# Leak_Detector_Remote.net
KiCad netlist of a schematic drawn in EAGLE
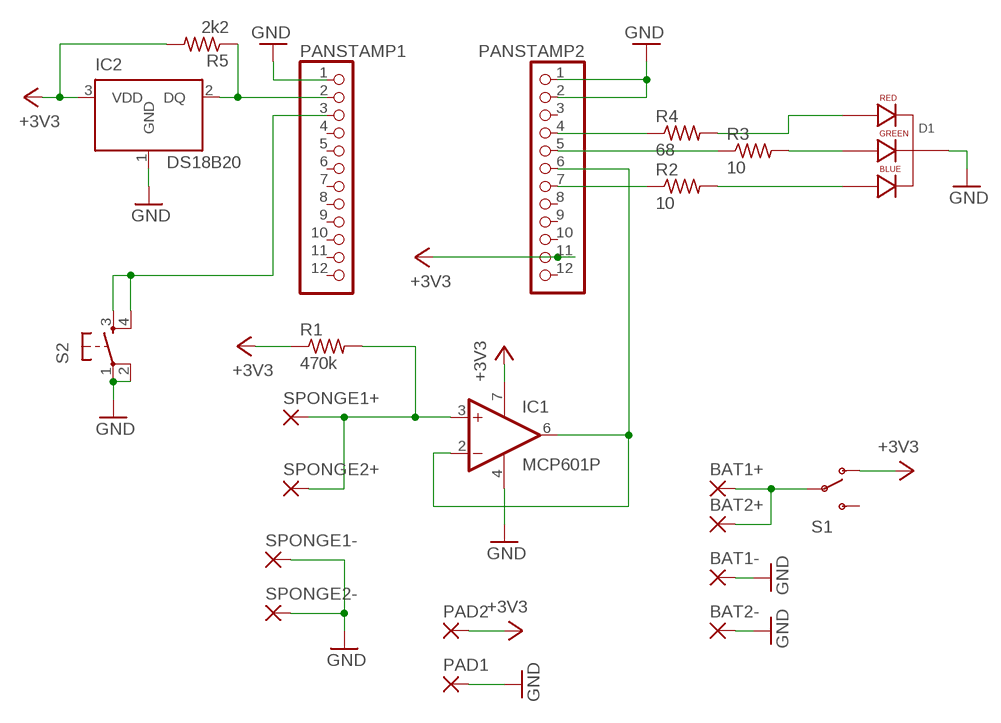
[diagram p0: schematic, sheet 1]

(export (version "E")
  (design (tool "Eeschema 10.0.6"))
  (components
    (comp (ref "BAT1+")
      (value "3,81/1,4")
      (footprint "eagle-import:3,81_1,4")
      (libsource (lib "eagle-import") (part "3,81/1,4"))
    )
    (comp (ref "BAT1-")
      (value "3,81/1,4")
      (footprint "eagle-import:3,81_1,4")
      (libsource (lib "eagle-import") (part "3,81/1,4"))
    )
    (comp (ref "BAT2+")
      (value "3,81/1,4")
      (footprint "eagle-import:3,81_1,4")
      (libsource (lib "eagle-import") (part "3,81/1,4"))
    )
    (comp (ref "BAT2-")
      (value "3,81/1,4")
      (footprint "eagle-import:3,81_1,4")
      (libsource (lib "eagle-import") (part "3,81/1,4"))
    )
    (comp (ref "D1")
      (value "LED-RGB-CC-THRUCLEAR")
      (footprint "eagle-import:LED-RGB-THRU")
      (libsource (lib "eagle-import") (part "LED-RGB-CC-THRUCLEAR"))
    )
    (comp (ref "IC1")
      (value "MCP601P")
      (footprint "eagle-import:DIL08")
      (libsource (lib "eagle-import") (part "MCP601P"))
    )
    (comp (ref "IC2")
      (value "DS18B20")
      (footprint "eagle-import:TO-92")
      (libsource (lib "eagle-import") (part "DS1820"))
    )
    (comp (ref "PAD1")
      (value "1,6/0,9")
      (footprint "eagle-import:1,6_0,9")
      (libsource (lib "eagle-import") (part "1,6/0,9"))
    )
    (comp (ref "PAD2")
      (value "1,6/0,9")
      (footprint "eagle-import:1,6_0,9")
      (libsource (lib "eagle-import") (part "1,6/0,9"))
    )
    (comp (ref "PANSTAMP1")
      (value "PINHD-1X12")
      (footprint "eagle-import:1X12")
      (libsource (lib "eagle-import") (part "PINHD-1X12"))
    )
    (comp (ref "PANSTAMP2")
      (value "PINHD-1X12")
      (footprint "eagle-import:1X12")
      (libsource (lib "eagle-import") (part "PINHD-1X12"))
    )
    (comp (ref "R1")
      (value "470k")
      (footprint "eagle-import:0204_7")
      (libsource (lib "eagle-import") (part "R-US_0204/7"))
    )
    (comp (ref "R2")
      (value "10")
      (footprint "eagle-import:0204_7")
      (libsource (lib "eagle-import") (part "R-US_0204/7"))
    )
    (comp (ref "R3")
      (value "10")
      (footprint "eagle-import:0204_7")
      (libsource (lib "eagle-import") (part "R-US_0204/7"))
    )
    (comp (ref "R4")
      (value "68")
      (footprint "eagle-import:0204_7")
      (libsource (lib "eagle-import") (part "R-US_0204/7"))
    )
    (comp (ref "R5")
      (value "2k2")
      (footprint "eagle-import:0204_7")
      (libsource (lib "eagle-import") (part "R-US_0204/7"))
    )
    (comp (ref "S1")
      (value "SWITCH-SPDTKIT")
      (footprint "eagle-import:SWITCH-SPDT_KIT")
      (libsource (lib "eagle-import") (part "SWITCH-SPDTKIT"))
    )
    (comp (ref "S2")
      (value "TAC_SWITCHPTH")
      (footprint "eagle-import:TACTILE-PTH")
      (libsource (lib "eagle-import") (part "TAC_SWITCHPTH"))
    )
    (comp (ref "SPONGE1+")
      (value "3,81/1,4")
      (footprint "eagle-import:3,81_1,4")
      (libsource (lib "eagle-import") (part "3,81/1,4"))
    )
    (comp (ref "SPONGE1-")
      (value "3,81/1,4")
      (footprint "eagle-import:3,81_1,4")
      (libsource (lib "eagle-import") (part "3,81/1,4"))
    )
    (comp (ref "SPONGE2+")
      (value "3,81/1,4")
      (footprint "eagle-import:3,81_1,4")
      (libsource (lib "eagle-import") (part "3,81/1,4"))
    )
    (comp (ref "SPONGE2-")
      (value "3,81/1,4")
      (footprint "eagle-import:3,81_1,4")
      (libsource (lib "eagle-import") (part "3,81/1,4"))
    )
  )
  (nets
    (net (code "1") (name "+3V3") (class "Default")
      (node (ref "IC1") (pin "7") (pinfunction "V+_7") (pintype "power_in"))
      (node (ref "IC2") (pin "3") (pinfunction "VDD_3") (pintype "input"))
      (node (ref "PAD2") (pin "1") (pinfunction "P_1") (pintype "passive"))
      (node (ref "PANSTAMP2") (pin "11") (pinfunction "11_11") (pintype "passive"))
      (node (ref "R1") (pin "1") (pinfunction "1_1") (pintype "passive"))
      (node (ref "R5") (pin "2") (pinfunction "2_2") (pintype "passive"))
      (node (ref "S1") (pin "1") (pinfunction "O_1") (pintype "passive"))
    )
    (net (code "2") (name "GND") (class "Default")
      (node (ref "BAT1-") (pin "1") (pinfunction "P_1") (pintype "passive"))
      (node (ref "BAT2-") (pin "1") (pinfunction "P_1") (pintype "passive"))
      (node (ref "D1") (pin "2") (pinfunction "CATHODE_2") (pintype "bidirectional"))
      (node (ref "IC1") (pin "4") (pinfunction "V-_4") (pintype "power_in"))
      (node (ref "IC2") (pin "1") (pinfunction "GND_1") (pintype "power_in"))
      (node (ref "PAD1") (pin "1") (pinfunction "P_1") (pintype "passive"))
      (node (ref "PANSTAMP1") (pin "1") (pinfunction "1_1") (pintype "passive"))
      (node (ref "PANSTAMP2") (pin "1") (pinfunction "1_1") (pintype "passive"))
      (node (ref "PANSTAMP2") (pin "2") (pinfunction "2_2") (pintype "passive"))
      (node (ref "S2") (pin "1") (pinfunction "1_1") (pintype "passive"))
      (node (ref "S2") (pin "2") (pinfunction "2_2") (pintype "passive"))
      (node (ref "SPONGE1-") (pin "1") (pinfunction "P_1") (pintype "passive"))
      (node (ref "SPONGE2-") (pin "1") (pinfunction "P_1") (pintype "passive"))
    )
    (net (code "3") (name "Net-(BAT1+-P)") (class "Default")
      (node (ref "BAT1+") (pin "1") (pinfunction "P_1") (pintype "passive"))
      (node (ref "BAT2+") (pin "1") (pinfunction "P_1") (pintype "passive"))
      (node (ref "S1") (pin "2") (pinfunction "P_2") (pintype "passive"))
    )
    (net (code "4") (name "Net-(D1-BLUE_CATHODE)") (class "Default")
      (node (ref "D1") (pin "4") (pinfunction "BLUE_CATHODE_4") (pintype "bidirectional"))
      (node (ref "R2") (pin "2") (pinfunction "2_2") (pintype "passive"))
    )
    (net (code "5") (name "Net-(D1-GREEN_CATHODE)") (class "Default")
      (node (ref "D1") (pin "3") (pinfunction "GREEN_CATHODE_3") (pintype "bidirectional"))
      (node (ref "R3") (pin "2") (pinfunction "2_2") (pintype "passive"))
    )
    (net (code "6") (name "Net-(D1-RED_CATHODE)") (class "Default")
      (node (ref "D1") (pin "1") (pinfunction "RED_CATHODE_1") (pintype "bidirectional"))
      (node (ref "R4") (pin "2") (pinfunction "2_2") (pintype "passive"))
    )
    (net (code "7") (name "Net-(IC1-+IN)") (class "Default")
      (node (ref "IC1") (pin "3") (pinfunction "+IN_3") (pintype "input"))
      (node (ref "R1") (pin "2") (pinfunction "2_2") (pintype "passive"))
      (node (ref "SPONGE1+") (pin "1") (pinfunction "P_1") (pintype "passive"))
      (node (ref "SPONGE2+") (pin "1") (pinfunction "P_1") (pintype "passive"))
    )
    (net (code "8") (name "Net-(IC1--IN)") (class "Default")
      (node (ref "IC1") (pin "2") (pinfunction "-IN_2") (pintype "input"))
      (node (ref "IC1") (pin "6") (pinfunction "OUT_6") (pintype "output"))
      (node (ref "PANSTAMP2") (pin "6") (pinfunction "6_6") (pintype "passive"))
    )
    (net (code "9") (name "Net-(IC2-DQ)") (class "Default")
      (node (ref "IC2") (pin "2") (pinfunction "DQ_2") (pintype "output"))
      (node (ref "PANSTAMP1") (pin "2") (pinfunction "2_2") (pintype "passive"))
      (node (ref "R5") (pin "1") (pinfunction "1_1") (pintype "passive"))
    )
    (net (code "10") (name "Net-(PANSTAMP1-Pad3)") (class "Default")
      (node (ref "PANSTAMP1") (pin "3") (pinfunction "3_3") (pintype "passive"))
      (node (ref "S2") (pin "3") (pinfunction "3_3") (pintype "passive"))
      (node (ref "S2") (pin "4") (pinfunction "4_4") (pintype "passive"))
    )
    (net (code "11") (name "Net-(PANSTAMP2-Pad4)") (class "Default")
      (node (ref "PANSTAMP2") (pin "4") (pinfunction "4_4") (pintype "passive"))
      (node (ref "R4") (pin "1") (pinfunction "1_1") (pintype "passive"))
    )
    (net (code "12") (name "Net-(PANSTAMP2-Pad5)") (class "Default")
      (node (ref "PANSTAMP2") (pin "5") (pinfunction "5_5") (pintype "passive"))
      (node (ref "R3") (pin "1") (pinfunction "1_1") (pintype "passive"))
    )
    (net (code "13") (name "Net-(PANSTAMP2-Pad7)") (class "Default")
      (node (ref "PANSTAMP2") (pin "7") (pinfunction "7_7") (pintype "passive"))
      (node (ref "R2") (pin "1") (pinfunction "1_1") (pintype "passive"))
    )
    (net (code "14") (name "unconnected-(PANSTAMP1-Pad4)") (class "Default")
      (node (ref "PANSTAMP1") (pin "4") (pinfunction "4_4") (pintype "passive"))
    )
    (net (code "15") (name "unconnected-(PANSTAMP1-Pad5)") (class "Default")
      (node (ref "PANSTAMP1") (pin "5") (pinfunction "5_5") (pintype "passive"))
    )
    (net (code "16") (name "unconnected-(PANSTAMP1-Pad6)") (class "Default")
      (node (ref "PANSTAMP1") (pin "6") (pinfunction "6_6") (pintype "passive"))
    )
    (net (code "17") (name "unconnected-(PANSTAMP1-Pad7)") (class "Default")
      (node (ref "PANSTAMP1") (pin "7") (pinfunction "7_7") (pintype "passive"))
    )
    (net (code "18") (name "unconnected-(PANSTAMP1-Pad8)") (class "Default")
      (node (ref "PANSTAMP1") (pin "8") (pinfunction "8_8") (pintype "passive"))
    )
    (net (code "19") (name "unconnected-(PANSTAMP1-Pad9)") (class "Default")
      (node (ref "PANSTAMP1") (pin "9") (pinfunction "9_9") (pintype "passive"))
    )
    (net (code "20") (name "unconnected-(PANSTAMP1-Pad10)") (class "Default")
      (node (ref "PANSTAMP1") (pin "10") (pinfunction "10_10") (pintype "passive"))
    )
    (net (code "21") (name "unconnected-(PANSTAMP1-Pad11)") (class "Default")
      (node (ref "PANSTAMP1") (pin "11") (pinfunction "11_11") (pintype "passive"))
    )
    (net (code "22") (name "unconnected-(PANSTAMP1-Pad12)") (class "Default")
      (node (ref "PANSTAMP1") (pin "12") (pinfunction "12_12") (pintype "passive"))
    )
    (net (code "23") (name "unconnected-(PANSTAMP2-Pad3)") (class "Default")
      (node (ref "PANSTAMP2") (pin "3") (pinfunction "3_3") (pintype "passive"))
    )
    (net (code "24") (name "unconnected-(PANSTAMP2-Pad8)") (class "Default")
      (node (ref "PANSTAMP2") (pin "8") (pinfunction "8_8") (pintype "passive"))
    )
    (net (code "25") (name "unconnected-(PANSTAMP2-Pad9)") (class "Default")
      (node (ref "PANSTAMP2") (pin "9") (pinfunction "9_9") (pintype "passive"))
    )
    (net (code "26") (name "unconnected-(PANSTAMP2-Pad10)") (class "Default")
      (node (ref "PANSTAMP2") (pin "10") (pinfunction "10_10") (pintype "passive"))
    )
    (net (code "27") (name "unconnected-(PANSTAMP2-Pad12)") (class "Default")
      (node (ref "PANSTAMP2") (pin "12") (pinfunction "12_12") (pintype "passive"))
    )
    (net (code "28") (name "unconnected-(S1-S-Pad3)") (class "Default")
      (node (ref "S1") (pin "3") (pinfunction "S_3") (pintype "passive"))
    )
  )
)
